# MainBoard.net
KiCad netlist of a schematic drawn in Altium Designer
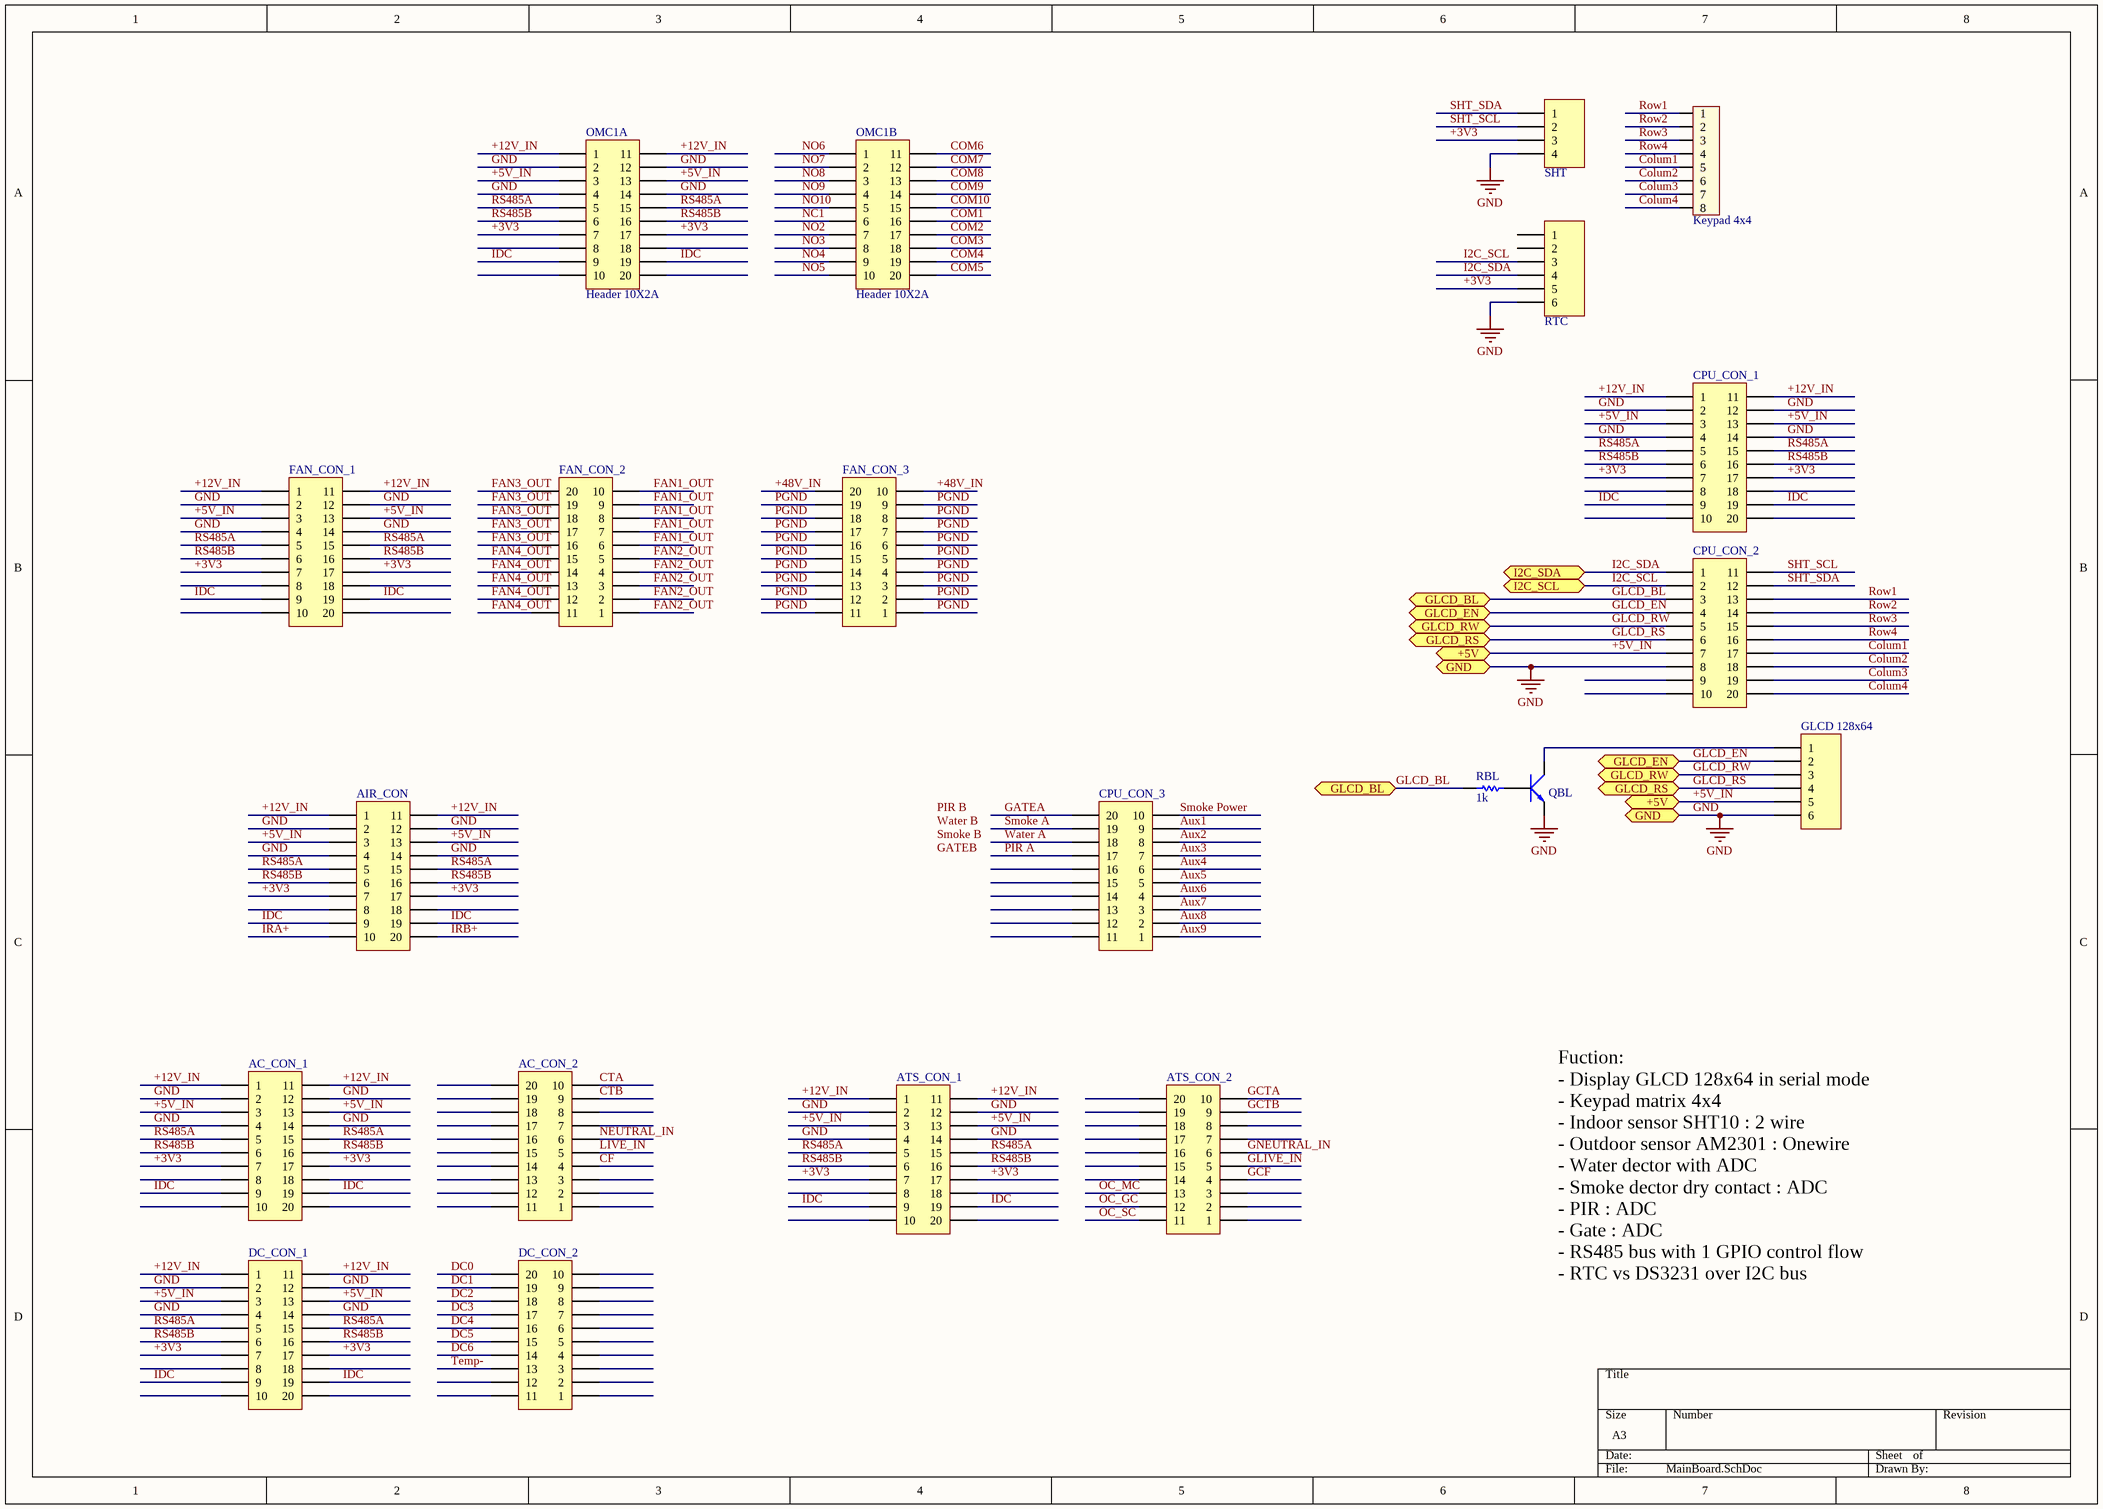
[diagram p0: MainBoard.SchDoc]

(export (version "E")
  (design (tool "Eeschema 10.0.6"))
  (components
    (comp (ref "AC_CON_1")
      (value "Header 10X2A")
      (footprint "HDR2X10_CEN")
      (description "Header, 10-Pin, Dual row")
      (fields (field (name "PUBLISHER") "Altium Limited"))
      (libsource (lib "Miscellaneous Connectors") (part "Header 10X2A"))
    )
    (comp (ref "AC_CON_2")
      (value "Header 10X2A")
      (footprint "HDR2X10_CEN")
      (description "Header, 10-Pin, Dual row")
      (fields (field (name "PUBLISHER") "Altium Limited"))
      (libsource (lib "") (part "Header 10X2A_1"))
    )
    (comp (ref "AIR_CON")
      (value "Header 10X2A")
      (footprint "HDR2X10_CEN")
      (description "Header, 10-Pin, Dual row")
      (fields (field (name "PUBLISHER") "Altium Limited"))
      (libsource (lib "Miscellaneous Connectors") (part "Header 10X2A"))
    )
    (comp (ref "ATS_CON_1")
      (value "Header 10X2A")
      (footprint "HDR2X10_CEN")
      (description "Header, 10-Pin, Dual row")
      (fields (field (name "PUBLISHER") "Altium Limited"))
      (libsource (lib "Miscellaneous Connectors") (part "Header 10X2A"))
    )
    (comp (ref "ATS_CON_2")
      (value "Header 10X2A")
      (footprint "HDR2X10_CEN")
      (description "Header, 10-Pin, Dual row")
      (fields (field (name "PUBLISHER") "Altium Limited"))
      (libsource (lib "") (part "Header 10X2A_1"))
    )
    (comp (ref "CPU_CON_1")
      (value "Header 10X2A")
      (footprint "HDR2X10_CEN")
      (description "Header, 10-Pin, Dual row")
      (fields (field (name "PUBLISHER") "Altium Limited"))
      (libsource (lib "Miscellaneous Connectors") (part "Header 10X2A"))
    )
    (comp (ref "CPU_CON_2")
      (value "Header 10X2A")
      (footprint "HDR2X10_CEN")
      (description "Header, 10-Pin, Dual row")
      (fields (field (name "PUBLISHER") "Altium Limited"))
      (libsource (lib "Miscellaneous Connectors") (part "Header 10X2A"))
    )
    (comp (ref "CPU_CON_3")
      (value "Header 10X2A")
      (footprint "HDR2X10_CEN")
      (description "Header, 10-Pin, Dual row")
      (fields (field (name "PUBLISHER") "Altium Limited"))
      (libsource (lib "") (part "Header 10X2A_1"))
    )
    (comp (ref "DC_CON_1")
      (value "Header 10X2A")
      (footprint "HDR2X10_CEN")
      (description "Header, 10-Pin, Dual row")
      (fields (field (name "PUBLISHER") "Altium Limited"))
      (libsource (lib "Miscellaneous Connectors") (part "Header 10X2A"))
    )
    (comp (ref "DC_CON_2")
      (value "Header 10X2A")
      (footprint "HDR2X10_CEN")
      (description "Header, 10-Pin, Dual row")
      (fields (field (name "PUBLISHER") "Altium Limited"))
      (libsource (lib "") (part "Header 10X2A_1"))
    )
    (comp (ref "FAN_CON_1")
      (value "Header 10X2A")
      (footprint "HDR2X10_CEN")
      (description "Header, 10-Pin, Dual row")
      (fields (field (name "PUBLISHER") "Altium Limited"))
      (libsource (lib "Miscellaneous Connectors") (part "Header 10X2A"))
    )
    (comp (ref "FAN_CON_2")
      (value "Header 10X2A")
      (footprint "HDR2X10_CEN")
      (description "Header, 10-Pin, Dual row")
      (fields (field (name "PUBLISHER") "Altium Limited"))
      (libsource (lib "") (part "Header 10X2A_1"))
    )
    (comp (ref "FAN_CON_3")
      (value "Header 10X2A")
      (footprint "HDR2X10_CEN")
      (description "Header, 10-Pin, Dual row")
      (fields (field (name "PUBLISHER") "Altium Limited"))
      (libsource (lib "") (part "Header 10X2A_1"))
    )
    (comp (ref "GLCD 128x64")
      (value "Header 6")
      (footprint "HDR1X6")
      (description "Header, 6-Pin")
      (fields (field (name "PUBLISHER") "Altium Limited"))
      (libsource (lib "Miscellaneous Connectors") (part "Header 6"))
    )
    (comp (ref "Keypad 4x4")
      (value "JP8")
      (footprint "CON8")
      (description "Connector 8")
      (libsource (lib "syhaunguyen") (part "Con8"))
    )
    (comp (ref "OMC1A")
      (value "Header 10X2A")
      (footprint "HDR2X10_CEN")
      (description "Header, 10-Pin, Dual row")
      (fields (field (name "PUBLISHER") "Altium Limited"))
      (libsource (lib "Miscellaneous Connectors") (part "Header 10X2A"))
    )
    (comp (ref "OMC1B")
      (value "Header 10X2A")
      (footprint "HDR2X10_CEN")
      (description "Header, 10-Pin, Dual row")
      (fields (field (name "PUBLISHER") "Altium Limited"))
      (libsource (lib "Miscellaneous Connectors") (part "Header 10X2A"))
    )
    (comp (ref "QBL")
      (value "C828")
      (footprint "SOT23 TOP")
      (description "Transistor C828 C1815....")
      (libsource (lib "Tuan") (part "NPN"))
    )
    (comp (ref "RBL")
      (value "1k")
      (footprint "RESC1608N_ZERO")
      (fields (field (name "Comment") "Res"))
      (libsource (lib "Tuan") (part "Res"))
    )
    (comp (ref "RTC")
      (value "Header 6")
      (footprint "heromap:HDR1X6")
      (description "Header, 6-Pin")
      (fields (field (name "PUBLISHER") "Altium Limited"))
      (libsource (lib "heromap") (part "Header 6"))
    )
    (comp (ref "SHT")
      (value "Header 4")
      (footprint "heromap:HDR1X4")
      (description "Header, 4-Pin")
      (fields (field (name "PUBLISHER") "Altium Limited"))
      (libsource (lib "heromap") (part "Header 4"))
    )
  )
  (nets
    (net (code "1") (name "/+3V3") (class "Default")
      (node (ref "AC_CON_1") (pin "17") (pinfunction "17_17") (pintype "passive"))
      (node (ref "AC_CON_1") (pin "7") (pinfunction "7_7") (pintype "passive"))
      (node (ref "AIR_CON") (pin "17") (pinfunction "17_17") (pintype "passive"))
      (node (ref "AIR_CON") (pin "7") (pinfunction "7_7") (pintype "passive"))
      (node (ref "ATS_CON_1") (pin "17") (pinfunction "17_17") (pintype "passive"))
      (node (ref "ATS_CON_1") (pin "7") (pinfunction "7_7") (pintype "passive"))
      (node (ref "CPU_CON_1") (pin "17") (pinfunction "17_17") (pintype "passive"))
      (node (ref "CPU_CON_1") (pin "7") (pinfunction "7_7") (pintype "passive"))
      (node (ref "DC_CON_1") (pin "17") (pinfunction "17_17") (pintype "passive"))
      (node (ref "DC_CON_1") (pin "7") (pinfunction "7_7") (pintype "passive"))
      (node (ref "FAN_CON_1") (pin "17") (pinfunction "17_17") (pintype "passive"))
      (node (ref "FAN_CON_1") (pin "7") (pinfunction "7_7") (pintype "passive"))
      (node (ref "OMC1A") (pin "17") (pinfunction "17_17") (pintype "passive"))
      (node (ref "OMC1A") (pin "7") (pinfunction "7_7") (pintype "passive"))
      (node (ref "RTC") (pin "5") (pinfunction "5_5") (pintype "passive"))
      (node (ref "SHT") (pin "3") (pinfunction "3_3") (pintype "passive"))
    )
    (net (code "2") (name "/+5V_IN") (class "Default")
      (node (ref "AC_CON_1") (pin "13") (pinfunction "13_13") (pintype "passive"))
      (node (ref "AC_CON_1") (pin "3") (pinfunction "3_3") (pintype "passive"))
      (node (ref "AIR_CON") (pin "13") (pinfunction "13_13") (pintype "passive"))
      (node (ref "AIR_CON") (pin "3") (pinfunction "3_3") (pintype "passive"))
      (node (ref "ATS_CON_1") (pin "13") (pinfunction "13_13") (pintype "passive"))
      (node (ref "ATS_CON_1") (pin "3") (pinfunction "3_3") (pintype "passive"))
      (node (ref "CPU_CON_1") (pin "13") (pinfunction "13_13") (pintype "passive"))
      (node (ref "CPU_CON_1") (pin "3") (pinfunction "3_3") (pintype "passive"))
      (node (ref "CPU_CON_2") (pin "7") (pinfunction "7_7") (pintype "passive"))
      (node (ref "DC_CON_1") (pin "13") (pinfunction "13_13") (pintype "passive"))
      (node (ref "DC_CON_1") (pin "3") (pinfunction "3_3") (pintype "passive"))
      (node (ref "FAN_CON_1") (pin "13") (pinfunction "13_13") (pintype "passive"))
      (node (ref "FAN_CON_1") (pin "3") (pinfunction "3_3") (pintype "passive"))
      (node (ref "GLCD 128x64") (pin "5") (pinfunction "5_5") (pintype "passive"))
      (node (ref "OMC1A") (pin "13") (pinfunction "13_13") (pintype "passive"))
      (node (ref "OMC1A") (pin "3") (pinfunction "3_3") (pintype "passive"))
    )
    (net (code "3") (name "/+12V_IN") (class "Default")
      (node (ref "AC_CON_1") (pin "1") (pinfunction "1_1") (pintype "passive"))
      (node (ref "AC_CON_1") (pin "11") (pinfunction "11_11") (pintype "passive"))
      (node (ref "AIR_CON") (pin "1") (pinfunction "1_1") (pintype "passive"))
      (node (ref "AIR_CON") (pin "11") (pinfunction "11_11") (pintype "passive"))
      (node (ref "ATS_CON_1") (pin "1") (pinfunction "1_1") (pintype "passive"))
      (node (ref "ATS_CON_1") (pin "11") (pinfunction "11_11") (pintype "passive"))
      (node (ref "CPU_CON_1") (pin "1") (pinfunction "1_1") (pintype "passive"))
      (node (ref "CPU_CON_1") (pin "11") (pinfunction "11_11") (pintype "passive"))
      (node (ref "DC_CON_1") (pin "1") (pinfunction "1_1") (pintype "passive"))
      (node (ref "DC_CON_1") (pin "11") (pinfunction "11_11") (pintype "passive"))
      (node (ref "FAN_CON_1") (pin "1") (pinfunction "1_1") (pintype "passive"))
      (node (ref "FAN_CON_1") (pin "11") (pinfunction "11_11") (pintype "passive"))
      (node (ref "OMC1A") (pin "1") (pinfunction "1_1") (pintype "passive"))
      (node (ref "OMC1A") (pin "11") (pinfunction "11_11") (pintype "passive"))
    )
    (net (code "4") (name "/+48V_IN") (class "Default")
      (node (ref "FAN_CON_3") (pin "10") (pinfunction "10_10") (pintype "passive"))
      (node (ref "FAN_CON_3") (pin "20") (pinfunction "20_20") (pintype "passive"))
    )
    (net (code "5") (name "/Aux1") (class "Default")
      (node (ref "CPU_CON_3") (pin "9") (pinfunction "9_9") (pintype "passive"))
    )
    (net (code "6") (name "/Aux2") (class "Default")
      (node (ref "CPU_CON_3") (pin "8") (pinfunction "8_8") (pintype "passive"))
    )
    (net (code "7") (name "/Aux3") (class "Default")
      (node (ref "CPU_CON_3") (pin "7") (pinfunction "7_7") (pintype "passive"))
    )
    (net (code "8") (name "/Aux4") (class "Default")
      (node (ref "CPU_CON_3") (pin "6") (pinfunction "6_6") (pintype "passive"))
    )
    (net (code "9") (name "/Aux5") (class "Default")
      (node (ref "CPU_CON_3") (pin "5") (pinfunction "5_5") (pintype "passive"))
    )
    (net (code "10") (name "/Aux6") (class "Default")
      (node (ref "CPU_CON_3") (pin "4") (pinfunction "4_4") (pintype "passive"))
    )
    (net (code "11") (name "/Aux7") (class "Default")
      (node (ref "CPU_CON_3") (pin "3") (pinfunction "3_3") (pintype "passive"))
    )
    (net (code "12") (name "/Aux8") (class "Default")
      (node (ref "CPU_CON_3") (pin "2") (pinfunction "2_2") (pintype "passive"))
    )
    (net (code "13") (name "/Aux9") (class "Default")
      (node (ref "CPU_CON_3") (pin "1") (pinfunction "1_1") (pintype "passive"))
    )
    (net (code "14") (name "/CF") (class "Default")
      (node (ref "AC_CON_2") (pin "4") (pinfunction "4_4") (pintype "passive"))
    )
    (net (code "15") (name "/COM1") (class "Default")
      (node (ref "OMC1B") (pin "16") (pinfunction "16_16") (pintype "passive"))
    )
    (net (code "16") (name "/COM2") (class "Default")
      (node (ref "OMC1B") (pin "17") (pinfunction "17_17") (pintype "passive"))
    )
    (net (code "17") (name "/COM3") (class "Default")
      (node (ref "OMC1B") (pin "18") (pinfunction "18_18") (pintype "passive"))
    )
    (net (code "18") (name "/COM4") (class "Default")
      (node (ref "OMC1B") (pin "19") (pinfunction "19_19") (pintype "passive"))
    )
    (net (code "19") (name "/COM5") (class "Default")
      (node (ref "OMC1B") (pin "20") (pinfunction "20_20") (pintype "passive"))
    )
    (net (code "20") (name "/COM6") (class "Default")
      (node (ref "OMC1B") (pin "11") (pinfunction "11_11") (pintype "passive"))
    )
    (net (code "21") (name "/COM7") (class "Default")
      (node (ref "OMC1B") (pin "12") (pinfunction "12_12") (pintype "passive"))
    )
    (net (code "22") (name "/COM8") (class "Default")
      (node (ref "OMC1B") (pin "13") (pinfunction "13_13") (pintype "passive"))
    )
    (net (code "23") (name "/COM9") (class "Default")
      (node (ref "OMC1B") (pin "14") (pinfunction "14_14") (pintype "passive"))
    )
    (net (code "24") (name "/COM10") (class "Default")
      (node (ref "OMC1B") (pin "15") (pinfunction "15_15") (pintype "passive"))
    )
    (net (code "25") (name "/CTA") (class "Default")
      (node (ref "AC_CON_2") (pin "10") (pinfunction "10_10") (pintype "passive"))
    )
    (net (code "26") (name "/CTB") (class "Default")
      (node (ref "AC_CON_2") (pin "9") (pinfunction "9_9") (pintype "passive"))
    )
    (net (code "27") (name "/Colum1") (class "Default")
      (node (ref "CPU_CON_2") (pin "17") (pinfunction "17_17") (pintype "passive"))
      (node (ref "Keypad 4x4") (pin "5") (pinfunction "5_5") (pintype "passive"))
    )
    (net (code "28") (name "/Colum2") (class "Default")
      (node (ref "CPU_CON_2") (pin "18") (pinfunction "18_18") (pintype "passive"))
      (node (ref "Keypad 4x4") (pin "6") (pinfunction "6_6") (pintype "passive"))
    )
    (net (code "29") (name "/Colum3") (class "Default")
      (node (ref "CPU_CON_2") (pin "19") (pinfunction "19_19") (pintype "passive"))
      (node (ref "Keypad 4x4") (pin "7") (pinfunction "7_7") (pintype "passive"))
    )
    (net (code "30") (name "/Colum4") (class "Default")
      (node (ref "CPU_CON_2") (pin "20") (pinfunction "20_20") (pintype "passive"))
      (node (ref "Keypad 4x4") (pin "8") (pinfunction "8_8") (pintype "passive"))
    )
    (net (code "31") (name "/DC0") (class "Default")
      (node (ref "DC_CON_2") (pin "20") (pinfunction "20_20") (pintype "passive"))
    )
    (net (code "32") (name "/DC1") (class "Default")
      (node (ref "DC_CON_2") (pin "19") (pinfunction "19_19") (pintype "passive"))
    )
    (net (code "33") (name "/DC2") (class "Default")
      (node (ref "DC_CON_2") (pin "18") (pinfunction "18_18") (pintype "passive"))
    )
    (net (code "34") (name "/DC3") (class "Default")
      (node (ref "DC_CON_2") (pin "17") (pinfunction "17_17") (pintype "passive"))
    )
    (net (code "35") (name "/DC4") (class "Default")
      (node (ref "DC_CON_2") (pin "16") (pinfunction "16_16") (pintype "passive"))
    )
    (net (code "36") (name "/DC5") (class "Default")
      (node (ref "DC_CON_2") (pin "15") (pinfunction "15_15") (pintype "passive"))
    )
    (net (code "37") (name "/DC6") (class "Default")
      (node (ref "DC_CON_2") (pin "14") (pinfunction "14_14") (pintype "passive"))
    )
    (net (code "38") (name "/FAN1_OUT") (class "Default")
      (node (ref "FAN_CON_2") (pin "10") (pinfunction "10_10") (pintype "passive"))
      (node (ref "FAN_CON_2") (pin "6") (pinfunction "6_6") (pintype "passive"))
      (node (ref "FAN_CON_2") (pin "7") (pinfunction "7_7") (pintype "passive"))
      (node (ref "FAN_CON_2") (pin "8") (pinfunction "8_8") (pintype "passive"))
      (node (ref "FAN_CON_2") (pin "9") (pinfunction "9_9") (pintype "passive"))
    )
    (net (code "39") (name "/FAN2_OUT") (class "Default")
      (node (ref "FAN_CON_2") (pin "1") (pinfunction "1_1") (pintype "passive"))
      (node (ref "FAN_CON_2") (pin "2") (pinfunction "2_2") (pintype "passive"))
      (node (ref "FAN_CON_2") (pin "3") (pinfunction "3_3") (pintype "passive"))
      (node (ref "FAN_CON_2") (pin "4") (pinfunction "4_4") (pintype "passive"))
      (node (ref "FAN_CON_2") (pin "5") (pinfunction "5_5") (pintype "passive"))
    )
    (net (code "40") (name "/FAN3_OUT") (class "Default")
      (node (ref "FAN_CON_2") (pin "16") (pinfunction "16_16") (pintype "passive"))
      (node (ref "FAN_CON_2") (pin "17") (pinfunction "17_17") (pintype "passive"))
      (node (ref "FAN_CON_2") (pin "18") (pinfunction "18_18") (pintype "passive"))
      (node (ref "FAN_CON_2") (pin "19") (pinfunction "19_19") (pintype "passive"))
      (node (ref "FAN_CON_2") (pin "20") (pinfunction "20_20") (pintype "passive"))
    )
    (net (code "41") (name "/FAN4_OUT") (class "Default")
      (node (ref "FAN_CON_2") (pin "11") (pinfunction "11_11") (pintype "passive"))
      (node (ref "FAN_CON_2") (pin "12") (pinfunction "12_12") (pintype "passive"))
      (node (ref "FAN_CON_2") (pin "13") (pinfunction "13_13") (pintype "passive"))
      (node (ref "FAN_CON_2") (pin "14") (pinfunction "14_14") (pintype "passive"))
      (node (ref "FAN_CON_2") (pin "15") (pinfunction "15_15") (pintype "passive"))
    )
    (net (code "42") (name "/GATEA") (class "Default")
      (node (ref "CPU_CON_3") (pin "20") (pinfunction "20_20") (pintype "passive"))
    )
    (net (code "44") (name "/GCF") (class "Default")
      (node (ref "ATS_CON_2") (pin "4") (pinfunction "4_4") (pintype "passive"))
    )
    (net (code "45") (name "/GCTA") (class "Default")
      (node (ref "ATS_CON_2") (pin "10") (pinfunction "10_10") (pintype "passive"))
    )
    (net (code "46") (name "/GCTB") (class "Default")
      (node (ref "ATS_CON_2") (pin "9") (pinfunction "9_9") (pintype "passive"))
    )
    (net (code "47") (name "/GLCD_BL") (class "Default")
      (node (ref "CPU_CON_2") (pin "3") (pinfunction "3_3") (pintype "passive"))
      (node (ref "RBL") (pin "1") (pinfunction "1_1") (pintype "passive"))
    )
    (net (code "48") (name "/GLCD_EN") (class "Default")
      (node (ref "CPU_CON_2") (pin "4") (pinfunction "4_4") (pintype "passive"))
      (node (ref "GLCD 128x64") (pin "2") (pinfunction "2_2") (pintype "passive"))
    )
    (net (code "49") (name "/GLCD_RS") (class "Default")
      (node (ref "CPU_CON_2") (pin "6") (pinfunction "6_6") (pintype "passive"))
      (node (ref "GLCD 128x64") (pin "4") (pinfunction "4_4") (pintype "passive"))
    )
    (net (code "50") (name "/GLCD_RW") (class "Default")
      (node (ref "CPU_CON_2") (pin "5") (pinfunction "5_5") (pintype "passive"))
      (node (ref "GLCD 128x64") (pin "3") (pinfunction "3_3") (pintype "passive"))
    )
    (net (code "51") (name "/GLIVE_IN") (class "Default")
      (node (ref "ATS_CON_2") (pin "5") (pinfunction "5_5") (pintype "passive"))
    )
    (net (code "52") (name "/GNEUTRAL_IN") (class "Default")
      (node (ref "ATS_CON_2") (pin "6") (pinfunction "6_6") (pintype "passive"))
    )
    (net (code "53") (name "/I2C_SCL") (class "Default")
      (node (ref "CPU_CON_2") (pin "2") (pinfunction "2_2") (pintype "passive"))
      (node (ref "RTC") (pin "3") (pinfunction "3_3") (pintype "passive"))
    )
    (net (code "54") (name "/I2C_SDA") (class "Default")
      (node (ref "CPU_CON_2") (pin "1") (pinfunction "1_1") (pintype "passive"))
      (node (ref "RTC") (pin "4") (pinfunction "4_4") (pintype "passive"))
    )
    (net (code "55") (name "/IDC") (class "Default")
      (node (ref "AC_CON_1") (pin "19") (pinfunction "19_19") (pintype "passive"))
      (node (ref "AC_CON_1") (pin "9") (pinfunction "9_9") (pintype "passive"))
      (node (ref "AIR_CON") (pin "19") (pinfunction "19_19") (pintype "passive"))
      (node (ref "AIR_CON") (pin "9") (pinfunction "9_9") (pintype "passive"))
      (node (ref "ATS_CON_1") (pin "19") (pinfunction "19_19") (pintype "passive"))
      (node (ref "ATS_CON_1") (pin "9") (pinfunction "9_9") (pintype "passive"))
      (node (ref "CPU_CON_1") (pin "19") (pinfunction "19_19") (pintype "passive"))
      (node (ref "CPU_CON_1") (pin "9") (pinfunction "9_9") (pintype "passive"))
      (node (ref "DC_CON_1") (pin "19") (pinfunction "19_19") (pintype "passive"))
      (node (ref "DC_CON_1") (pin "9") (pinfunction "9_9") (pintype "passive"))
      (node (ref "FAN_CON_1") (pin "19") (pinfunction "19_19") (pintype "passive"))
      (node (ref "FAN_CON_1") (pin "9") (pinfunction "9_9") (pintype "passive"))
      (node (ref "OMC1A") (pin "19") (pinfunction "19_19") (pintype "passive"))
      (node (ref "OMC1A") (pin "9") (pinfunction "9_9") (pintype "passive"))
    )
    (net (code "56") (name "/IRA+") (class "Default")
      (node (ref "AIR_CON") (pin "10") (pinfunction "10_10") (pintype "passive"))
    )
    (net (code "57") (name "/IRB+") (class "Default")
      (node (ref "AIR_CON") (pin "20") (pinfunction "20_20") (pintype "passive"))
    )
    (net (code "58") (name "/LIVE_IN") (class "Default")
      (node (ref "AC_CON_2") (pin "5") (pinfunction "5_5") (pintype "passive"))
    )
    (net (code "59") (name "/NC1") (class "Default")
      (node (ref "OMC1B") (pin "6") (pinfunction "6_6") (pintype "passive"))
    )
    (net (code "60") (name "/NEUTRAL_IN") (class "Default")
      (node (ref "AC_CON_2") (pin "6") (pinfunction "6_6") (pintype "passive"))
    )
    (net (code "61") (name "/NO2") (class "Default")
      (node (ref "OMC1B") (pin "7") (pinfunction "7_7") (pintype "passive"))
    )
    (net (code "62") (name "/NO3") (class "Default")
      (node (ref "OMC1B") (pin "8") (pinfunction "8_8") (pintype "passive"))
    )
    (net (code "63") (name "/NO4") (class "Default")
      (node (ref "OMC1B") (pin "9") (pinfunction "9_9") (pintype "passive"))
    )
    (net (code "64") (name "/NO5") (class "Default")
      (node (ref "OMC1B") (pin "10") (pinfunction "10_10") (pintype "passive"))
    )
    (net (code "65") (name "/NO6") (class "Default")
      (node (ref "OMC1B") (pin "1") (pinfunction "1_1") (pintype "passive"))
    )
    (net (code "66") (name "/NO7") (class "Default")
      (node (ref "OMC1B") (pin "2") (pinfunction "2_2") (pintype "passive"))
    )
    (net (code "67") (name "/NO8") (class "Default")
      (node (ref "OMC1B") (pin "3") (pinfunction "3_3") (pintype "passive"))
    )
    (net (code "68") (name "/NO9") (class "Default")
      (node (ref "OMC1B") (pin "4") (pinfunction "4_4") (pintype "passive"))
    )
    (net (code "69") (name "/NO10") (class "Default")
      (node (ref "OMC1B") (pin "5") (pinfunction "5_5") (pintype "passive"))
    )
    (net (code "70") (name "/OC_GC") (class "Default")
      (node (ref "ATS_CON_2") (pin "12") (pinfunction "12_12") (pintype "passive"))
    )
    (net (code "71") (name "/OC_MC") (class "Default")
      (node (ref "ATS_CON_2") (pin "13") (pinfunction "13_13") (pintype "passive"))
    )
    (net (code "72") (name "/OC_SC") (class "Default")
      (node (ref "ATS_CON_2") (pin "11") (pinfunction "11_11") (pintype "passive"))
    )
    (net (code "73") (name "/PGND") (class "Default")
      (node (ref "FAN_CON_3") (pin "1") (pinfunction "1_1") (pintype "passive"))
      (node (ref "FAN_CON_3") (pin "11") (pinfunction "11_11") (pintype "passive"))
      (node (ref "FAN_CON_3") (pin "12") (pinfunction "12_12") (pintype "passive"))
      (node (ref "FAN_CON_3") (pin "13") (pinfunction "13_13") (pintype "passive"))
      (node (ref "FAN_CON_3") (pin "14") (pinfunction "14_14") (pintype "passive"))
      (node (ref "FAN_CON_3") (pin "15") (pinfunction "15_15") (pintype "passive"))
      (node (ref "FAN_CON_3") (pin "16") (pinfunction "16_16") (pintype "passive"))
      (node (ref "FAN_CON_3") (pin "17") (pinfunction "17_17") (pintype "passive"))
      (node (ref "FAN_CON_3") (pin "18") (pinfunction "18_18") (pintype "passive"))
      (node (ref "FAN_CON_3") (pin "19") (pinfunction "19_19") (pintype "passive"))
      (node (ref "FAN_CON_3") (pin "2") (pinfunction "2_2") (pintype "passive"))
      (node (ref "FAN_CON_3") (pin "3") (pinfunction "3_3") (pintype "passive"))
      (node (ref "FAN_CON_3") (pin "4") (pinfunction "4_4") (pintype "passive"))
      (node (ref "FAN_CON_3") (pin "5") (pinfunction "5_5") (pintype "passive"))
      (node (ref "FAN_CON_3") (pin "6") (pinfunction "6_6") (pintype "passive"))
      (node (ref "FAN_CON_3") (pin "7") (pinfunction "7_7") (pintype "passive"))
      (node (ref "FAN_CON_3") (pin "8") (pinfunction "8_8") (pintype "passive"))
      (node (ref "FAN_CON_3") (pin "9") (pinfunction "9_9") (pintype "passive"))
    )
    (net (code "74") (name "/PIR A") (class "Default")
      (node (ref "CPU_CON_3") (pin "17") (pinfunction "17_17") (pintype "passive"))
    )
    (net (code "76") (name "/RS485A") (class "Default")
      (node (ref "AC_CON_1") (pin "15") (pinfunction "15_15") (pintype "passive"))
      (node (ref "AC_CON_1") (pin "5") (pinfunction "5_5") (pintype "passive"))
      (node (ref "AIR_CON") (pin "15") (pinfunction "15_15") (pintype "passive"))
      (node (ref "AIR_CON") (pin "5") (pinfunction "5_5") (pintype "passive"))
      (node (ref "ATS_CON_1") (pin "15") (pinfunction "15_15") (pintype "passive"))
      (node (ref "ATS_CON_1") (pin "5") (pinfunction "5_5") (pintype "passive"))
      (node (ref "CPU_CON_1") (pin "15") (pinfunction "15_15") (pintype "passive"))
      (node (ref "CPU_CON_1") (pin "5") (pinfunction "5_5") (pintype "passive"))
      (node (ref "DC_CON_1") (pin "15") (pinfunction "15_15") (pintype "passive"))
      (node (ref "DC_CON_1") (pin "5") (pinfunction "5_5") (pintype "passive"))
      (node (ref "FAN_CON_1") (pin "15") (pinfunction "15_15") (pintype "passive"))
      (node (ref "FAN_CON_1") (pin "5") (pinfunction "5_5") (pintype "passive"))
      (node (ref "OMC1A") (pin "15") (pinfunction "15_15") (pintype "passive"))
      (node (ref "OMC1A") (pin "5") (pinfunction "5_5") (pintype "passive"))
    )
    (net (code "77") (name "/RS485B") (class "Default")
      (node (ref "AC_CON_1") (pin "16") (pinfunction "16_16") (pintype "passive"))
      (node (ref "AC_CON_1") (pin "6") (pinfunction "6_6") (pintype "passive"))
      (node (ref "AIR_CON") (pin "16") (pinfunction "16_16") (pintype "passive"))
      (node (ref "AIR_CON") (pin "6") (pinfunction "6_6") (pintype "passive"))
      (node (ref "ATS_CON_1") (pin "16") (pinfunction "16_16") (pintype "passive"))
      (node (ref "ATS_CON_1") (pin "6") (pinfunction "6_6") (pintype "passive"))
      (node (ref "CPU_CON_1") (pin "16") (pinfunction "16_16") (pintype "passive"))
      (node (ref "CPU_CON_1") (pin "6") (pinfunction "6_6") (pintype "passive"))
      (node (ref "DC_CON_1") (pin "16") (pinfunction "16_16") (pintype "passive"))
      (node (ref "DC_CON_1") (pin "6") (pinfunction "6_6") (pintype "passive"))
      (node (ref "FAN_CON_1") (pin "16") (pinfunction "16_16") (pintype "passive"))
      (node (ref "FAN_CON_1") (pin "6") (pinfunction "6_6") (pintype "passive"))
      (node (ref "OMC1A") (pin "16") (pinfunction "16_16") (pintype "passive"))
      (node (ref "OMC1A") (pin "6") (pinfunction "6_6") (pintype "passive"))
    )
    (net (code "78") (name "/Row1") (class "Default")
      (node (ref "CPU_CON_2") (pin "13") (pinfunction "13_13") (pintype "passive"))
      (node (ref "Keypad 4x4") (pin "1") (pinfunction "1_1") (pintype "passive"))
    )
    (net (code "79") (name "/Row2") (class "Default")
      (node (ref "CPU_CON_2") (pin "14") (pinfunction "14_14") (pintype "passive"))
      (node (ref "Keypad 4x4") (pin "2") (pinfunction "2_2") (pintype "passive"))
    )
    (net (code "80") (name "/Row3") (class "Default")
      (node (ref "CPU_CON_2") (pin "15") (pinfunction "15_15") (pintype "passive"))
      (node (ref "Keypad 4x4") (pin "3") (pinfunction "3_3") (pintype "passive"))
    )
    (net (code "81") (name "/Row4") (class "Default")
      (node (ref "CPU_CON_2") (pin "16") (pinfunction "16_16") (pintype "passive"))
      (node (ref "Keypad 4x4") (pin "4") (pinfunction "4_4") (pintype "passive"))
    )
    (net (code "82") (name "/SHT_SCL") (class "Default")
      (node (ref "CPU_CON_2") (pin "11") (pinfunction "11_11") (pintype "passive"))
      (node (ref "SHT") (pin "2") (pinfunction "2_2") (pintype "passive"))
    )
    (net (code "83") (name "/SHT_SDA") (class "Default")
      (node (ref "CPU_CON_2") (pin "12") (pinfunction "12_12") (pintype "passive"))
      (node (ref "SHT") (pin "1") (pinfunction "1_1") (pintype "passive"))
    )
    (net (code "84") (name "/Smoke A") (class "Default")
      (node (ref "CPU_CON_3") (pin "19") (pinfunction "19_19") (pintype "passive"))
    )
    (net (code "86") (name "/Smoke Power") (class "Default")
      (node (ref "CPU_CON_3") (pin "10") (pinfunction "10_10") (pintype "passive"))
    )
    (net (code "87") (name "/Temp-") (class "Default")
      (node (ref "DC_CON_2") (pin "13") (pinfunction "13_13") (pintype "passive"))
    )
    (net (code "88") (name "/Water A") (class "Default")
      (node (ref "CPU_CON_3") (pin "18") (pinfunction "18_18") (pintype "passive"))
    )
    (net (code "90") (name "GND") (class "Default")
      (node (ref "AC_CON_1") (pin "12") (pinfunction "12_12") (pintype "passive"))
      (node (ref "AC_CON_1") (pin "14") (pinfunction "14_14") (pintype "passive"))
      (node (ref "AC_CON_1") (pin "2") (pinfunction "2_2") (pintype "passive"))
      (node (ref "AC_CON_1") (pin "4") (pinfunction "4_4") (pintype "passive"))
      (node (ref "AIR_CON") (pin "12") (pinfunction "12_12") (pintype "passive"))
      (node (ref "AIR_CON") (pin "14") (pinfunction "14_14") (pintype "passive"))
      (node (ref "AIR_CON") (pin "2") (pinfunction "2_2") (pintype "passive"))
      (node (ref "AIR_CON") (pin "4") (pinfunction "4_4") (pintype "passive"))
      (node (ref "ATS_CON_1") (pin "12") (pinfunction "12_12") (pintype "passive"))
      (node (ref "ATS_CON_1") (pin "14") (pinfunction "14_14") (pintype "passive"))
      (node (ref "ATS_CON_1") (pin "2") (pinfunction "2_2") (pintype "passive"))
      (node (ref "ATS_CON_1") (pin "4") (pinfunction "4_4") (pintype "passive"))
      (node (ref "CPU_CON_1") (pin "12") (pinfunction "12_12") (pintype "passive"))
      (node (ref "CPU_CON_1") (pin "14") (pinfunction "14_14") (pintype "passive"))
      (node (ref "CPU_CON_1") (pin "2") (pinfunction "2_2") (pintype "passive"))
      (node (ref "CPU_CON_1") (pin "4") (pinfunction "4_4") (pintype "passive"))
      (node (ref "CPU_CON_2") (pin "8") (pinfunction "8_8") (pintype "passive"))
      (node (ref "DC_CON_1") (pin "12") (pinfunction "12_12") (pintype "passive"))
      (node (ref "DC_CON_1") (pin "14") (pinfunction "14_14") (pintype "passive"))
      (node (ref "DC_CON_1") (pin "2") (pinfunction "2_2") (pintype "passive"))
      (node (ref "DC_CON_1") (pin "4") (pinfunction "4_4") (pintype "passive"))
      (node (ref "FAN_CON_1") (pin "12") (pinfunction "12_12") (pintype "passive"))
      (node (ref "FAN_CON_1") (pin "14") (pinfunction "14_14") (pintype "passive"))
      (node (ref "FAN_CON_1") (pin "2") (pinfunction "2_2") (pintype "passive"))
      (node (ref "FAN_CON_1") (pin "4") (pinfunction "4_4") (pintype "passive"))
      (node (ref "GLCD 128x64") (pin "6") (pinfunction "6_6") (pintype "passive"))
      (node (ref "OMC1A") (pin "12") (pinfunction "12_12") (pintype "passive"))
      (node (ref "OMC1A") (pin "14") (pinfunction "14_14") (pintype "passive"))
      (node (ref "OMC1A") (pin "2") (pinfunction "2_2") (pintype "passive"))
      (node (ref "OMC1A") (pin "4") (pinfunction "4_4") (pintype "passive"))
      (node (ref "QBL") (pin "3") (pinfunction "E_3") (pintype "passive"))
      (node (ref "RTC") (pin "6") (pinfunction "6_6") (pintype "passive"))
      (node (ref "SHT") (pin "4") (pinfunction "4_4") (pintype "passive"))
    )
    (net (code "91") (name "Net-(QBL-B)") (class "Default")
      (node (ref "QBL") (pin "1") (pinfunction "B_1") (pintype "passive"))
      (node (ref "RBL") (pin "2") (pinfunction "2_2") (pintype "passive"))
    )
    (net (code "92") (name "Net-(QBL-C)") (class "Default")
      (node (ref "GLCD 128x64") (pin "1") (pinfunction "1_1") (pintype "passive"))
      (node (ref "QBL") (pin "2") (pinfunction "C_2") (pintype "passive"))
    )
    (net (code "93") (name "unconnected-(AC_CON_1-Pad8)") (class "Default")
      (node (ref "AC_CON_1") (pin "8") (pinfunction "8_8") (pintype "passive"))
    )
    (net (code "94") (name "unconnected-(AC_CON_1-Pad10)") (class "Default")
      (node (ref "AC_CON_1") (pin "10") (pinfunction "10_10") (pintype "passive"))
    )
    (net (code "95") (name "unconnected-(AC_CON_1-Pad18)") (class "Default")
      (node (ref "AC_CON_1") (pin "18") (pinfunction "18_18") (pintype "passive"))
    )
    (net (code "96") (name "unconnected-(AC_CON_1-Pad20)") (class "Default")
      (node (ref "AC_CON_1") (pin "20") (pinfunction "20_20") (pintype "passive"))
    )
    (net (code "97") (name "unconnected-(AC_CON_2-Pad1)") (class "Default")
      (node (ref "AC_CON_2") (pin "1") (pinfunction "1_1") (pintype "passive"))
    )
    (net (code "98") (name "unconnected-(AC_CON_2-Pad2)") (class "Default")
      (node (ref "AC_CON_2") (pin "2") (pinfunction "2_2") (pintype "passive"))
    )
    (net (code "99") (name "unconnected-(AC_CON_2-Pad3)") (class "Default")
      (node (ref "AC_CON_2") (pin "3") (pinfunction "3_3") (pintype "passive"))
    )
    (net (code "100") (name "unconnected-(AC_CON_2-Pad7)") (class "Default")
      (node (ref "AC_CON_2") (pin "7") (pinfunction "7_7") (pintype "passive"))
    )
    (net (code "101") (name "unconnected-(AC_CON_2-Pad8)") (class "Default")
      (node (ref "AC_CON_2") (pin "8") (pinfunction "8_8") (pintype "passive"))
    )
    (net (code "102") (name "unconnected-(AC_CON_2-Pad11)") (class "Default")
      (node (ref "AC_CON_2") (pin "11") (pinfunction "11_11") (pintype "passive"))
    )
    (net (code "103") (name "unconnected-(AC_CON_2-Pad12)") (class "Default")
      (node (ref "AC_CON_2") (pin "12") (pinfunction "12_12") (pintype "passive"))
    )
    (net (code "104") (name "unconnected-(AC_CON_2-Pad13)") (class "Default")
      (node (ref "AC_CON_2") (pin "13") (pinfunction "13_13") (pintype "passive"))
    )
    (net (code "105") (name "unconnected-(AC_CON_2-Pad14)") (class "Default")
      (node (ref "AC_CON_2") (pin "14") (pinfunction "14_14") (pintype "passive"))
    )
    (net (code "106") (name "unconnected-(AC_CON_2-Pad15)") (class "Default")
      (node (ref "AC_CON_2") (pin "15") (pinfunction "15_15") (pintype "passive"))
    )
    (net (code "107") (name "unconnected-(AC_CON_2-Pad16)") (class "Default")
      (node (ref "AC_CON_2") (pin "16") (pinfunction "16_16") (pintype "passive"))
    )
    (net (code "108") (name "unconnected-(AC_CON_2-Pad17)") (class "Default")
      (node (ref "AC_CON_2") (pin "17") (pinfunction "17_17") (pintype "passive"))
    )
    (net (code "109") (name "unconnected-(AC_CON_2-Pad18)") (class "Default")
      (node (ref "AC_CON_2") (pin "18") (pinfunction "18_18") (pintype "passive"))
    )
    (net (code "110") (name "unconnected-(AC_CON_2-Pad19)") (class "Default")
      (node (ref "AC_CON_2") (pin "19") (pinfunction "19_19") (pintype "passive"))
    )
    (net (code "111") (name "unconnected-(AC_CON_2-Pad20)") (class "Default")
      (node (ref "AC_CON_2") (pin "20") (pinfunction "20_20") (pintype "passive"))
    )
    (net (code "112") (name "unconnected-(AIR_CON-Pad8)") (class "Default")
      (node (ref "AIR_CON") (pin "8") (pinfunction "8_8") (pintype "passive"))
    )
    (net (code "113") (name "unconnected-(AIR_CON-Pad18)") (class "Default")
      (node (ref "AIR_CON") (pin "18") (pinfunction "18_18") (pintype "passive"))
    )
    (net (code "114") (name "unconnected-(ATS_CON_1-Pad8)") (class "Default")
      (node (ref "ATS_CON_1") (pin "8") (pinfunction "8_8") (pintype "passive"))
    )
    (net (code "115") (name "unconnected-(ATS_CON_1-Pad10)") (class "Default")
      (node (ref "ATS_CON_1") (pin "10") (pinfunction "10_10") (pintype "passive"))
    )
    (net (code "116") (name "unconnected-(ATS_CON_1-Pad18)") (class "Default")
      (node (ref "ATS_CON_1") (pin "18") (pinfunction "18_18") (pintype "passive"))
    )
    (net (code "117") (name "unconnected-(ATS_CON_1-Pad20)") (class "Default")
      (node (ref "ATS_CON_1") (pin "20") (pinfunction "20_20") (pintype "passive"))
    )
    (net (code "118") (name "unconnected-(ATS_CON_2-Pad1)") (class "Default")
      (node (ref "ATS_CON_2") (pin "1") (pinfunction "1_1") (pintype "passive"))
    )
    (net (code "119") (name "unconnected-(ATS_CON_2-Pad2)") (class "Default")
      (node (ref "ATS_CON_2") (pin "2") (pinfunction "2_2") (pintype "passive"))
    )
    (net (code "120") (name "unconnected-(ATS_CON_2-Pad3)") (class "Default")
      (node (ref "ATS_CON_2") (pin "3") (pinfunction "3_3") (pintype "passive"))
    )
    (net (code "121") (name "unconnected-(ATS_CON_2-Pad7)") (class "Default")
      (node (ref "ATS_CON_2") (pin "7") (pinfunction "7_7") (pintype "passive"))
    )
    (net (code "122") (name "unconnected-(ATS_CON_2-Pad8)") (class "Default")
      (node (ref "ATS_CON_2") (pin "8") (pinfunction "8_8") (pintype "passive"))
    )
    (net (code "123") (name "unconnected-(ATS_CON_2-Pad14)") (class "Default")
      (node (ref "ATS_CON_2") (pin "14") (pinfunction "14_14") (pintype "passive"))
    )
    (net (code "124") (name "unconnected-(ATS_CON_2-Pad15)") (class "Default")
      (node (ref "ATS_CON_2") (pin "15") (pinfunction "15_15") (pintype "passive"))
    )
    (net (code "125") (name "unconnected-(ATS_CON_2-Pad16)") (class "Default")
      (node (ref "ATS_CON_2") (pin "16") (pinfunction "16_16") (pintype "passive"))
    )
    (net (code "126") (name "unconnected-(ATS_CON_2-Pad17)") (class "Default")
      (node (ref "ATS_CON_2") (pin "17") (pinfunction "17_17") (pintype "passive"))
    )
    (net (code "127") (name "unconnected-(ATS_CON_2-Pad18)") (class "Default")
      (node (ref "ATS_CON_2") (pin "18") (pinfunction "18_18") (pintype "passive"))
    )
    (net (code "128") (name "unconnected-(ATS_CON_2-Pad19)") (class "Default")
      (node (ref "ATS_CON_2") (pin "19") (pinfunction "19_19") (pintype "passive"))
    )
    (net (code "129") (name "unconnected-(ATS_CON_2-Pad20)") (class "Default")
      (node (ref "ATS_CON_2") (pin "20") (pinfunction "20_20") (pintype "passive"))
    )
    (net (code "130") (name "unconnected-(CPU_CON_1-Pad8)") (class "Default")
      (node (ref "CPU_CON_1") (pin "8") (pinfunction "8_8") (pintype "passive"))
    )
    (net (code "131") (name "unconnected-(CPU_CON_1-Pad10)") (class "Default")
      (node (ref "CPU_CON_1") (pin "10") (pinfunction "10_10") (pintype "passive"))
    )
    (net (code "132") (name "unconnected-(CPU_CON_1-Pad18)") (class "Default")
      (node (ref "CPU_CON_1") (pin "18") (pinfunction "18_18") (pintype "passive"))
    )
    (net (code "133") (name "unconnected-(CPU_CON_1-Pad20)") (class "Default")
      (node (ref "CPU_CON_1") (pin "20") (pinfunction "20_20") (pintype "passive"))
    )
    (net (code "134") (name "unconnected-(CPU_CON_2-Pad9)") (class "Default")
      (node (ref "CPU_CON_2") (pin "9") (pinfunction "9_9") (pintype "passive"))
    )
    (net (code "135") (name "unconnected-(CPU_CON_2-Pad10)") (class "Default")
      (node (ref "CPU_CON_2") (pin "10") (pinfunction "10_10") (pintype "passive"))
    )
    (net (code "136") (name "unconnected-(CPU_CON_3-Pad11)") (class "Default")
      (node (ref "CPU_CON_3") (pin "11") (pinfunction "11_11") (pintype "passive"))
    )
    (net (code "137") (name "unconnected-(CPU_CON_3-Pad12)") (class "Default")
      (node (ref "CPU_CON_3") (pin "12") (pinfunction "12_12") (pintype "passive"))
    )
    (net (code "138") (name "unconnected-(CPU_CON_3-Pad13)") (class "Default")
      (node (ref "CPU_CON_3") (pin "13") (pinfunction "13_13") (pintype "passive"))
    )
    (net (code "139") (name "unconnected-(CPU_CON_3-Pad14)") (class "Default")
      (node (ref "CPU_CON_3") (pin "14") (pinfunction "14_14") (pintype "passive"))
    )
    (net (code "140") (name "unconnected-(CPU_CON_3-Pad15)") (class "Default")
      (node (ref "CPU_CON_3") (pin "15") (pinfunction "15_15") (pintype "passive"))
    )
    (net (code "141") (name "unconnected-(CPU_CON_3-Pad16)") (class "Default")
      (node (ref "CPU_CON_3") (pin "16") (pinfunction "16_16") (pintype "passive"))
    )
    (net (code "142") (name "unconnected-(DC_CON_1-Pad8)") (class "Default")
      (node (ref "DC_CON_1") (pin "8") (pinfunction "8_8") (pintype "passive"))
    )
    (net (code "143") (name "unconnected-(DC_CON_1-Pad10)") (class "Default")
      (node (ref "DC_CON_1") (pin "10") (pinfunction "10_10") (pintype "passive"))
    )
    (net (code "144") (name "unconnected-(DC_CON_1-Pad18)") (class "Default")
      (node (ref "DC_CON_1") (pin "18") (pinfunction "18_18") (pintype "passive"))
    )
    (net (code "145") (name "unconnected-(DC_CON_1-Pad20)") (class "Default")
      (node (ref "DC_CON_1") (pin "20") (pinfunction "20_20") (pintype "passive"))
    )
    (net (code "146") (name "unconnected-(DC_CON_2-Pad1)") (class "Default")
      (node (ref "DC_CON_2") (pin "1") (pinfunction "1_1") (pintype "passive"))
    )
    (net (code "147") (name "unconnected-(DC_CON_2-Pad2)") (class "Default")
      (node (ref "DC_CON_2") (pin "2") (pinfunction "2_2") (pintype "passive"))
    )
    (net (code "148") (name "unconnected-(DC_CON_2-Pad3)") (class "Default")
      (node (ref "DC_CON_2") (pin "3") (pinfunction "3_3") (pintype "passive"))
    )
    (net (code "149") (name "unconnected-(DC_CON_2-Pad4)") (class "Default")
      (node (ref "DC_CON_2") (pin "4") (pinfunction "4_4") (pintype "passive"))
    )
    (net (code "150") (name "unconnected-(DC_CON_2-Pad5)") (class "Default")
      (node (ref "DC_CON_2") (pin "5") (pinfunction "5_5") (pintype "passive"))
    )
    (net (code "151") (name "unconnected-(DC_CON_2-Pad6)") (class "Default")
      (node (ref "DC_CON_2") (pin "6") (pinfunction "6_6") (pintype "passive"))
    )
    (net (code "152") (name "unconnected-(DC_CON_2-Pad7)") (class "Default")
      (node (ref "DC_CON_2") (pin "7") (pinfunction "7_7") (pintype "passive"))
    )
    (net (code "153") (name "unconnected-(DC_CON_2-Pad8)") (class "Default")
      (node (ref "DC_CON_2") (pin "8") (pinfunction "8_8") (pintype "passive"))
    )
    (net (code "154") (name "unconnected-(DC_CON_2-Pad9)") (class "Default")
      (node (ref "DC_CON_2") (pin "9") (pinfunction "9_9") (pintype "passive"))
    )
    (net (code "155") (name "unconnected-(DC_CON_2-Pad10)") (class "Default")
      (node (ref "DC_CON_2") (pin "10") (pinfunction "10_10") (pintype "passive"))
    )
    (net (code "156") (name "unconnected-(DC_CON_2-Pad11)") (class "Default")
      (node (ref "DC_CON_2") (pin "11") (pinfunction "11_11") (pintype "passive"))
    )
    (net (code "157") (name "unconnected-(DC_CON_2-Pad12)") (class "Default")
      (node (ref "DC_CON_2") (pin "12") (pinfunction "12_12") (pintype "passive"))
    )
    (net (code "158") (name "unconnected-(FAN_CON_1-Pad8)") (class "Default")
      (node (ref "FAN_CON_1") (pin "8") (pinfunction "8_8") (pintype "passive"))
    )
    (net (code "159") (name "unconnected-(FAN_CON_1-Pad10)") (class "Default")
      (node (ref "FAN_CON_1") (pin "10") (pinfunction "10_10") (pintype "passive"))
    )
    (net (code "160") (name "unconnected-(FAN_CON_1-Pad18)") (class "Default")
      (node (ref "FAN_CON_1") (pin "18") (pinfunction "18_18") (pintype "passive"))
    )
    (net (code "161") (name "unconnected-(FAN_CON_1-Pad20)") (class "Default")
      (node (ref "FAN_CON_1") (pin "20") (pinfunction "20_20") (pintype "passive"))
    )
    (net (code "162") (name "unconnected-(OMC1A-Pad8)") (class "Default")
      (node (ref "OMC1A") (pin "8") (pinfunction "8_8") (pintype "passive"))
    )
    (net (code "163") (name "unconnected-(OMC1A-Pad10)") (class "Default")
      (node (ref "OMC1A") (pin "10") (pinfunction "10_10") (pintype "passive"))
    )
    (net (code "164") (name "unconnected-(OMC1A-Pad18)") (class "Default")
      (node (ref "OMC1A") (pin "18") (pinfunction "18_18") (pintype "passive"))
    )
    (net (code "165") (name "unconnected-(OMC1A-Pad20)") (class "Default")
      (node (ref "OMC1A") (pin "20") (pinfunction "20_20") (pintype "passive"))
    )
    (net (code "166") (name "unconnected-(RTC-Pad1)") (class "Default")
      (node (ref "RTC") (pin "1") (pinfunction "1_1") (pintype "passive"))
    )
    (net (code "167") (name "unconnected-(RTC-Pad2)") (class "Default")
      (node (ref "RTC") (pin "2") (pinfunction "2_2") (pintype "passive"))
    )
  )
)
